# LM2596-5V-BuckConverter-copy_2024-10-14.net
KiCad netlist of a schematic drawn in Altium Designer
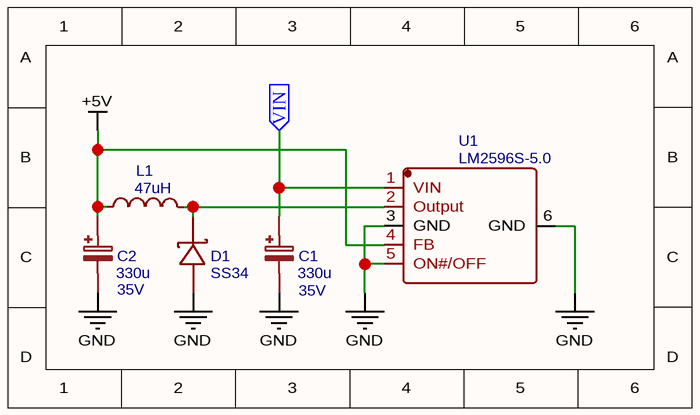
[diagram p0: LM2596-5V-BuckConverter-copy_2024-10-14.schdoc]

(export (version "E")
  (design (tool "Eeschema 10.0.6"))
  (components
    (comp (ref "C1")
      (value "330u")
      (fields (field (name "MANUFACTURER PART") "?") (field (name "CONTRIBUTOR") "EasyEDA"))
      (libsource (lib "altium-import") (part "root_0_330u_"))
    )
    (comp (ref "C2")
      (value "330u")
      (fields (field (name "MANUFACTURER PART") "?") (field (name "CONTRIBUTOR") "EasyEDA"))
      (libsource (lib "altium-import") (part "root_0_330u_"))
    )
    (comp (ref "D1")
      (value "SS34")
      (fields (field (name "MANUFACTURER") "Yenji") (field (name "CONTRIBUTOR") "LCSC"))
      (libsource (lib "altium-import") (part "root_1_SS34_"))
    )
    (comp (ref "L1")
      (value "47uH")
      (fields
        (field (name "MANUFACTURER") "Sumida")
        (field (name "MANUFACTURER PART") "CDRH127NP-470MC")
        (field (name "CONTRIBUTOR") "LCSC")
      )
      (libsource (lib "altium-import") (part "root_0_47uH_"))
    )
    (comp (ref "U1")
      (value "LM2596S-5.0")
      (fields
        (field (name "MANUFACTURER") "Texas Instruments")
        (field (name "MANUFACTURER PART") "LM2596S-5.0/NOPB")
        (field (name "CONTRIBUTOR") "LCSC")
      )
      (libsource (lib "altium-import") (part "root_0_LM2596S-5.0_"))
    )
  )
  (nets
    (net (code "1") (name "+5V") (class "Default")
      (node (ref "C2") (pin "1") (pinfunction "1_1") (pintype "passive"))
      (node (ref "L1") (pin "1") (pinfunction "1_1") (pintype "passive"))
      (node (ref "U1") (pin "4") (pinfunction "FB_4") (pintype "passive"))
    )
    (net (code "2") (name "/VIN") (class "Default")
      (node (ref "C1") (pin "1") (pinfunction "1_1") (pintype "passive"))
      (node (ref "U1") (pin "1") (pinfunction "VIN_1") (pintype "passive"))
    )
    (net (code "3") (name "GND") (class "Default")
      (node (ref "C1") (pin "2") (pinfunction "2_2") (pintype "passive"))
      (node (ref "C2") (pin "2") (pinfunction "2_2") (pintype "passive"))
      (node (ref "D1") (pin "1") (pinfunction "A_1") (pintype "passive"))
      (node (ref "U1") (pin "3") (pinfunction "GND_3") (pintype "passive"))
      (node (ref "U1") (pin "5") (pinfunction "ON#/OFF_5") (pintype "passive"))
      (node (ref "U1") (pin "6") (pinfunction "GND_6") (pintype "passive"))
    )
    (net (code "4") (name "Net-(D1-K)") (class "Default")
      (node (ref "D1") (pin "2") (pinfunction "K_2") (pintype "passive"))
      (node (ref "L1") (pin "2") (pinfunction "2_2") (pintype "passive"))
      (node (ref "U1") (pin "2") (pinfunction "Output_2") (pintype "passive"))
    )
  )
)
